# CONNECTIONS.net
KiCad netlist of a schematic drawn in Altium Designer
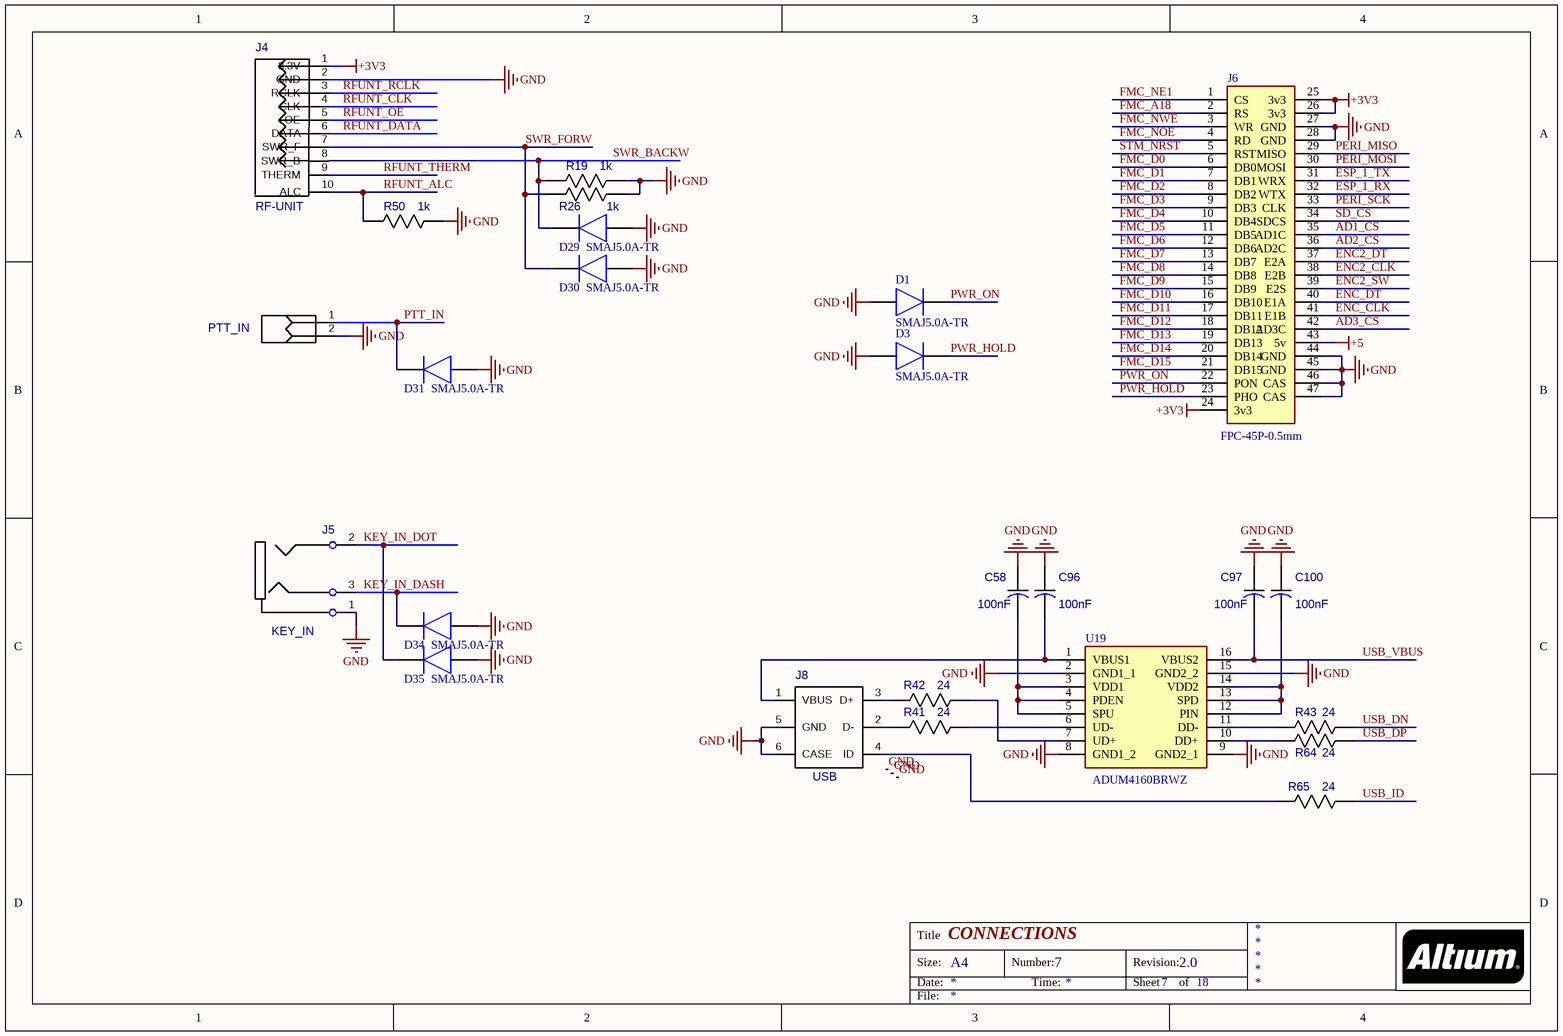
[diagram p0: CONNECTIONS.SchDoc]

(export (version "E")
  (design (tool "Eeschema 10.0.6"))
  (components
    (comp (ref "C58")
      (value "100nF")
      (footprint "CAP_0805")
      (description "CAP_0805")
      (libsource (lib "*") (part "CAP_0805"))
    )
    (comp (ref "C96")
      (value "100nF")
      (footprint "CAP_0805")
      (description "CAP_0805")
      (libsource (lib "*") (part "CAP_0805"))
    )
    (comp (ref "C97")
      (value "100nF")
      (footprint "CAP_0805")
      (description "CAP_0805")
      (libsource (lib "*") (part "CAP_0805"))
    )
    (comp (ref "C100")
      (value "100nF")
      (footprint "CAP_0805")
      (description "CAP_0805")
      (libsource (lib "*") (part "CAP_0805"))
    )
    (comp (ref "D1")
      (value "SMAJ5.0A-TR")
      (footprint "SMBJ36CATR")
      (description "Diode")
      (fields
        (field (name "MANUFACTURER_PART_NUMBER") "SMLVT3V3")
        (field (name "MOUSER PART NUMBER") "511-SMLVT3V3")
      )
      (libsource (lib "*") (part "SMLVT3V3"))
    )
    (comp (ref "D3")
      (value "SMAJ5.0A-TR")
      (footprint "SMBJ36CATR")
      (description "Diode")
      (fields
        (field (name "MANUFACTURER_PART_NUMBER") "SMLVT3V3")
        (field (name "MOUSER PART NUMBER") "511-SMLVT3V3")
      )
      (libsource (lib "*") (part "SMLVT3V3"))
    )
    (comp (ref "D29")
      (value "SMAJ5.0A-TR")
      (footprint "SamacSys:SMBJ36CATR")
      (description "Diode")
      (fields
        (field (name "MANUFACTURER_PART_NUMBER") "SMLVT3V3")
        (field (name "MOUSER PART NUMBER") "511-SMLVT3V3")
      )
      (libsource (lib "*") (part "SMLVT3V3"))
    )
    (comp (ref "D30")
      (value "SMAJ5.0A-TR")
      (footprint "SMBJ36CATR")
      (description "Diode")
      (fields
        (field (name "MANUFACTURER_PART_NUMBER") "SMLVT3V3")
        (field (name "MOUSER PART NUMBER") "511-SMLVT3V3")
      )
      (libsource (lib "*") (part "SMLVT3V3"))
    )
    (comp (ref "D31")
      (value "SMAJ5.0A-TR")
      (footprint "SamacSys:SMBJ36CATR")
      (description "Diode")
      (fields
        (field (name "MANUFACTURER_PART_NUMBER") "SMLVT3V3")
        (field (name "MOUSER PART NUMBER") "511-SMLVT3V3")
      )
      (libsource (lib "*") (part "SMLVT3V3"))
    )
    (comp (ref "D34")
      (value "SMAJ5.0A-TR")
      (footprint "SamacSys:SMBJ36CATR")
      (description "Diode")
      (fields
        (field (name "MANUFACTURER_PART_NUMBER") "SMLVT3V3")
        (field (name "MOUSER PART NUMBER") "511-SMLVT3V3")
      )
      (libsource (lib "*") (part "SMLVT3V3"))
    )
    (comp (ref "D35")
      (value "SMAJ5.0A-TR")
      (footprint "SamacSys:SMBJ36CATR")
      (description "Diode")
      (fields
        (field (name "MANUFACTURER_PART_NUMBER") "SMLVT3V3")
        (field (name "MOUSER PART NUMBER") "511-SMLVT3V3")
      )
      (libsource (lib "*") (part "SMLVT3V3"))
    )
    (comp (ref "J4")
      (value "RF-UNIT")
      (footprint "90131-0126")
      (description "2*5 Pin")
      (libsource (lib "MOTHERBOARD") (part "90131-0126"))
    )
    (comp (ref "J5")
      (value "KEY_IN")
      (footprint "SJ1-3525NG")
      (description "SJ1-3525NG")
      (libsource (lib "*") (part "SJ1-3523N"))
    )
    (comp (ref "J6")
      (value "FPC-45P-0.5mm")
      (footprint "MOTHERBOARD:FH12S45S05SH60")
      (description "Connector")
      (fields
        (field (name "MANUFACTURER_PART_NUMBER") "FH12S-45S-0.5SH(55)")
        (field (name "MOUSER PART NUMBER") "798-FH12S-45S-05SH55")
      )
      (libsource (lib "*") (part "FH12S-45S-0.5SH_55_"))
    )
    (comp (ref "J8")
      (value "USB")
      (footprint "2-1734035-3")
      (description "2-1734035-3")
      (libsource (lib "*") (part "2-1734035-3"))
    )
    (comp (ref "PTT_IN")
      (value "PTT_IN")
      (footprint "51022-0200")
      (description "51022-0200")
      (libsource (lib "*") (part "51022-0200"))
    )
    (comp (ref "R19")
      (value "1k")
      (footprint "RES_0805")
      (description "RES_0805")
      (libsource (lib "*") (part "RES_0805"))
    )
    (comp (ref "R26")
      (value "1k")
      (footprint "RES_0805")
      (description "RES_0805")
      (libsource (lib "*") (part "RES_0805"))
    )
    (comp (ref "R41")
      (value "24")
      (footprint "RES_0805")
      (description "RES_0805")
      (libsource (lib "*") (part "RES_0805"))
    )
    (comp (ref "R42")
      (value "24")
      (footprint "RES_0805")
      (description "RES_0805")
      (libsource (lib "*") (part "RES_0805"))
    )
    (comp (ref "R43")
      (value "24")
      (footprint "RES_0805")
      (description "RES_0805")
      (libsource (lib "*") (part "RES_0805"))
    )
    (comp (ref "R50")
      (value "1k")
      (footprint "RES_0805")
      (description "RES_0805")
      (libsource (lib "*") (part "RES_0805"))
    )
    (comp (ref "R64")
      (value "24")
      (footprint "RES_0805")
      (description "RES_0805")
      (libsource (lib "*") (part "RES_0805"))
    )
    (comp (ref "R65")
      (value "24")
      (footprint "RES_0805")
      (description "RES_0805")
      (libsource (lib "*") (part "RES_0805"))
    )
    (comp (ref "U19")
      (value "ADUM4160BRWZ")
      (footprint "SOIC127P1032X265-16N")
      (description "Integrated Circuit")
      (fields (field (name "MOUSER PART NUMBER") "584-ADUM4160BRWZ"))
      (libsource (lib "*") (part "ADUM4160BRWZ"))
    )
  )
  (nets
    (net (code "1") (name "+3V3") (class "Default")
      (node (ref "J4") (pin "1") (pinfunction "3.3V_1") (pintype "passive"))
      (node (ref "J6") (pin "24") (pinfunction "3v3_24") (pintype "passive"))
      (node (ref "J6") (pin "25") (pinfunction "3v3_25") (pintype "passive"))
      (node (ref "J6") (pin "26") (pinfunction "3v3_26") (pintype "passive"))
    )
    (net (code "2") (name "+5") (class "Default")
      (node (ref "J6") (pin "43") (pinfunction "5v_43") (pintype "passive"))
    )
    (net (code "3") (name "/AD1_CS") (class "Default")
      (node (ref "J6") (pin "35") (pinfunction "AD1C_35") (pintype "passive"))
    )
    (net (code "4") (name "/AD2_CS") (class "Default")
      (node (ref "J6") (pin "36") (pinfunction "AD2C_36") (pintype "passive"))
    )
    (net (code "5") (name "/AD3_CS") (class "Default")
      (node (ref "J6") (pin "42") (pinfunction "AD3C_42") (pintype "passive"))
    )
    (net (code "6") (name "/ENC2_CLK") (class "Default")
      (node (ref "J6") (pin "38") (pinfunction "E2B_38") (pintype "passive"))
    )
    (net (code "7") (name "/ENC2_DT") (class "Default")
      (node (ref "J6") (pin "37") (pinfunction "E2A_37") (pintype "passive"))
    )
    (net (code "8") (name "/ENC2_SW") (class "Default")
      (node (ref "J6") (pin "39") (pinfunction "E2S_39") (pintype "passive"))
    )
    (net (code "9") (name "/ENC_CLK") (class "Default")
      (node (ref "J6") (pin "41") (pinfunction "E1B_41") (pintype "passive"))
    )
    (net (code "10") (name "/ENC_DT") (class "Default")
      (node (ref "J6") (pin "40") (pinfunction "E1A_40") (pintype "passive"))
    )
    (net (code "11") (name "/ESP_1_RX") (class "Default")
      (node (ref "J6") (pin "32") (pinfunction "WTX_32") (pintype "passive"))
    )
    (net (code "12") (name "/ESP_1_TX") (class "Default")
      (node (ref "J6") (pin "31") (pinfunction "WRX_31") (pintype "passive"))
    )
    (net (code "13") (name "/FMC_A18") (class "Default")
      (node (ref "J6") (pin "2") (pinfunction "RS_2") (pintype "passive"))
    )
    (net (code "14") (name "/FMC_D0") (class "Default")
      (node (ref "J6") (pin "6") (pinfunction "DB0_6") (pintype "passive"))
    )
    (net (code "15") (name "/FMC_D1") (class "Default")
      (node (ref "J6") (pin "7") (pinfunction "DB1_7") (pintype "passive"))
    )
    (net (code "16") (name "/FMC_D2") (class "Default")
      (node (ref "J6") (pin "8") (pinfunction "DB2_8") (pintype "passive"))
    )
    (net (code "17") (name "/FMC_D3") (class "Default")
      (node (ref "J6") (pin "9") (pinfunction "DB3_9") (pintype "passive"))
    )
    (net (code "18") (name "/FMC_D4") (class "Default")
      (node (ref "J6") (pin "10") (pinfunction "DB4_10") (pintype "passive"))
    )
    (net (code "19") (name "/FMC_D5") (class "Default")
      (node (ref "J6") (pin "11") (pinfunction "DB5_11") (pintype "passive"))
    )
    (net (code "20") (name "/FMC_D6") (class "Default")
      (node (ref "J6") (pin "12") (pinfunction "DB6_12") (pintype "passive"))
    )
    (net (code "21") (name "/FMC_D7") (class "Default")
      (node (ref "J6") (pin "13") (pinfunction "DB7_13") (pintype "passive"))
    )
    (net (code "22") (name "/FMC_D8") (class "Default")
      (node (ref "J6") (pin "14") (pinfunction "DB8_14") (pintype "passive"))
    )
    (net (code "23") (name "/FMC_D9") (class "Default")
      (node (ref "J6") (pin "15") (pinfunction "DB9_15") (pintype "passive"))
    )
    (net (code "24") (name "/FMC_D10") (class "Default")
      (node (ref "J6") (pin "16") (pinfunction "DB10_16") (pintype "passive"))
    )
    (net (code "25") (name "/FMC_D11") (class "Default")
      (node (ref "J6") (pin "17") (pinfunction "DB11_17") (pintype "passive"))
    )
    (net (code "26") (name "/FMC_D12") (class "Default")
      (node (ref "J6") (pin "18") (pinfunction "DB12_18") (pintype "passive"))
    )
    (net (code "27") (name "/FMC_D13") (class "Default")
      (node (ref "J6") (pin "19") (pinfunction "DB13_19") (pintype "passive"))
    )
    (net (code "28") (name "/FMC_D14") (class "Default")
      (node (ref "J6") (pin "20") (pinfunction "DB14_20") (pintype "passive"))
    )
    (net (code "29") (name "/FMC_D15") (class "Default")
      (node (ref "J6") (pin "21") (pinfunction "DB15_21") (pintype "passive"))
    )
    (net (code "30") (name "/FMC_NE1") (class "Default")
      (node (ref "J6") (pin "1") (pinfunction "CS_1") (pintype "passive"))
    )
    (net (code "31") (name "/FMC_NOE") (class "Default")
      (node (ref "J6") (pin "4") (pinfunction "RD_4") (pintype "passive"))
    )
    (net (code "32") (name "/FMC_NWE") (class "Default")
      (node (ref "J6") (pin "3") (pinfunction "WR_3") (pintype "passive"))
    )
    (net (code "33") (name "/KEY_IN_DASH") (class "Default")
      (node (ref "D34") (pin "1") (pinfunction "K_1") (pintype "passive"))
      (node (ref "J5") (pin "3") (pinfunction "ring_3") (pintype "passive"))
    )
    (net (code "34") (name "/KEY_IN_DOT") (class "Default")
      (node (ref "D35") (pin "1") (pinfunction "K_1") (pintype "passive"))
      (node (ref "J5") (pin "2") (pinfunction "tip_2") (pintype "passive"))
    )
    (net (code "35") (name "/PERI_MISO") (class "Default")
      (node (ref "J6") (pin "29") (pinfunction "MISO_29") (pintype "passive"))
    )
    (net (code "36") (name "/PERI_MOSI") (class "Default")
      (node (ref "J6") (pin "30") (pinfunction "MOSI_30") (pintype "passive"))
    )
    (net (code "37") (name "/PERI_SCK") (class "Default")
      (node (ref "J6") (pin "33") (pinfunction "CLK_33") (pintype "passive"))
    )
    (net (code "38") (name "/PTT_IN") (class "Default")
      (node (ref "D31") (pin "1") (pinfunction "K_1") (pintype "passive"))
      (node (ref "PTT_IN") (pin "1") (pinfunction "1_1") (pintype "passive"))
    )
    (net (code "39") (name "/PWR_HOLD") (class "Default")
      (node (ref "D3") (pin "1") (pinfunction "K_1") (pintype "passive"))
      (node (ref "J6") (pin "23") (pinfunction "PHO_23") (pintype "passive"))
    )
    (net (code "40") (name "/PWR_ON") (class "Default")
      (node (ref "D1") (pin "1") (pinfunction "K_1") (pintype "passive"))
      (node (ref "J6") (pin "22") (pinfunction "PON_22") (pintype "passive"))
    )
    (net (code "41") (name "/RFUNT_ALC") (class "Default")
      (node (ref "J4") (pin "10") (pinfunction "ALC_10") (pintype "passive"))
      (node (ref "R50") (pin "1") (pinfunction "1_1") (pintype "passive"))
    )
    (net (code "42") (name "/RFUNT_CLK") (class "Default")
      (node (ref "J4") (pin "4") (pinfunction "CLK_4") (pintype "passive"))
    )
    (net (code "43") (name "/RFUNT_DATA") (class "Default")
      (node (ref "J4") (pin "6") (pinfunction "DATA_6") (pintype "passive"))
    )
    (net (code "44") (name "/RFUNT_OE") (class "Default")
      (node (ref "J4") (pin "5") (pinfunction "OE_5") (pintype "passive"))
    )
    (net (code "45") (name "/RFUNT_RCLK") (class "Default")
      (node (ref "J4") (pin "3") (pinfunction "RCLK_3") (pintype "passive"))
    )
    (net (code "46") (name "/RFUNT_THERM") (class "Default")
      (node (ref "J4") (pin "9") (pinfunction "THERM_9") (pintype "passive"))
    )
    (net (code "47") (name "/SD_CS") (class "Default")
      (node (ref "J6") (pin "34") (pinfunction "SDCS_34") (pintype "passive"))
    )
    (net (code "48") (name "/STM_NRST") (class "Default")
      (node (ref "J6") (pin "5") (pinfunction "RST_5") (pintype "passive"))
    )
    (net (code "49") (name "/SWR_BACKW") (class "Default")
      (node (ref "D29") (pin "1") (pinfunction "K_1") (pintype "passive"))
      (node (ref "J4") (pin "8") (pinfunction "SWR_B_8") (pintype "passive"))
      (node (ref "R19") (pin "1") (pinfunction "1_1") (pintype "passive"))
    )
    (net (code "50") (name "/SWR_FORW") (class "Default")
      (node (ref "D30") (pin "1") (pinfunction "K_1") (pintype "passive"))
      (node (ref "J4") (pin "7") (pinfunction "SWR_F_7") (pintype "passive"))
      (node (ref "R26") (pin "1") (pinfunction "1_1") (pintype "passive"))
    )
    (net (code "51") (name "/USB_DN") (class "Default")
      (node (ref "R43") (pin "2") (pinfunction "2_2") (pintype "passive"))
    )
    (net (code "52") (name "/USB_DP") (class "Default")
      (node (ref "R64") (pin "2") (pinfunction "2_2") (pintype "passive"))
    )
    (net (code "53") (name "/USB_ID") (class "Default")
      (node (ref "R65") (pin "2") (pinfunction "2_2") (pintype "passive"))
    )
    (net (code "54") (name "/USB_VBUS") (class "Default")
      (node (ref "C97") (pin "2") (pinfunction "2_2") (pintype "passive"))
      (node (ref "U19") (pin "16") (pinfunction "VBUS2_16") (pintype "passive"))
    )
    (net (code "55") (name "GND") (class "Default")
      (node (ref "C100") (pin "1") (pinfunction "1_1") (pintype "passive"))
      (node (ref "C58") (pin "1") (pinfunction "1_1") (pintype "passive"))
      (node (ref "C96") (pin "1") (pinfunction "1_1") (pintype "passive"))
      (node (ref "C97") (pin "1") (pinfunction "1_1") (pintype "passive"))
      (node (ref "D1") (pin "2") (pinfunction "A_2") (pintype "passive"))
      (node (ref "D29") (pin "2") (pinfunction "A_2") (pintype "passive"))
      (node (ref "D3") (pin "2") (pinfunction "A_2") (pintype "passive"))
      (node (ref "D30") (pin "2") (pinfunction "A_2") (pintype "passive"))
      (node (ref "D31") (pin "2") (pinfunction "A_2") (pintype "passive"))
      (node (ref "D34") (pin "2") (pinfunction "A_2") (pintype "passive"))
      (node (ref "D35") (pin "2") (pinfunction "A_2") (pintype "passive"))
      (node (ref "J4") (pin "2") (pinfunction "GND_2") (pintype "passive"))
      (node (ref "J5") (pin "1") (pinfunction "sleeve_1") (pintype "passive"))
      (node (ref "J6") (pin "27") (pinfunction "GND_27") (pintype "passive"))
      (node (ref "J6") (pin "28") (pinfunction "GND_28") (pintype "passive"))
      (node (ref "J6") (pin "44") (pinfunction "GND_44") (pintype "passive"))
      (node (ref "J6") (pin "45") (pinfunction "GND_45") (pintype "passive"))
      (node (ref "J6") (pin "46") (pinfunction "CAS_46") (pintype "passive"))
      (node (ref "J6") (pin "47") (pinfunction "CAS_47") (pintype "passive"))
      (node (ref "J8") (pin "5") (pinfunction "GND_5") (pintype "passive"))
      (node (ref "J8") (pin "6") (pinfunction "CASE_6") (pintype "passive"))
      (node (ref "J8") (pin "7") (pinfunction "0_7") (pintype "passive"))
      (node (ref "J8") (pin "8") (pinfunction "0_8") (pintype "passive"))
      (node (ref "J8") (pin "9") (pinfunction "0_9") (pintype "passive"))
      (node (ref "PTT_IN") (pin "2") (pinfunction "2_2") (pintype "passive"))
      (node (ref "R19") (pin "2") (pinfunction "2_2") (pintype "passive"))
      (node (ref "R26") (pin "2") (pinfunction "2_2") (pintype "passive"))
      (node (ref "R50") (pin "2") (pinfunction "2_2") (pintype "passive"))
      (node (ref "U19") (pin "15") (pinfunction "GND2_2_15") (pintype "passive"))
      (node (ref "U19") (pin "2") (pinfunction "GND1_1_2") (pintype "passive"))
      (node (ref "U19") (pin "8") (pinfunction "GND1_2_8") (pintype "passive"))
      (node (ref "U19") (pin "9") (pinfunction "GND2_1_9") (pintype "passive"))
    )
    (net (code "56") (name "Net-(J8-D+)") (class "Default")
      (node (ref "J8") (pin "3") (pinfunction "D+_3") (pintype "passive"))
      (node (ref "R42") (pin "1") (pinfunction "1_1") (pintype "passive"))
    )
    (net (code "57") (name "Net-(J8-D-)") (class "Default")
      (node (ref "J8") (pin "2") (pinfunction "D-_2") (pintype "passive"))
      (node (ref "R41") (pin "1") (pinfunction "1_1") (pintype "passive"))
    )
    (net (code "58") (name "Net-(J8-ID)") (class "Default")
      (node (ref "J8") (pin "4") (pinfunction "ID_4") (pintype "passive"))
      (node (ref "R65") (pin "1") (pinfunction "1_1") (pintype "passive"))
    )
    (net (code "59") (name "Net-(J8-VBUS)") (class "Default")
      (node (ref "C96") (pin "2") (pinfunction "2_2") (pintype "passive"))
      (node (ref "J8") (pin "1") (pinfunction "VBUS_1") (pintype "passive"))
      (node (ref "U19") (pin "1") (pinfunction "VBUS1_1") (pintype "passive"))
    )
    (net (code "60") (name "Net-(U19-DD+)") (class "Default")
      (node (ref "R64") (pin "1") (pinfunction "1_1") (pintype "passive"))
      (node (ref "U19") (pin "10") (pinfunction "DD+_10") (pintype "passive"))
    )
    (net (code "61") (name "Net-(U19-DD-)") (class "Default")
      (node (ref "R43") (pin "1") (pinfunction "1_1") (pintype "passive"))
      (node (ref "U19") (pin "11") (pinfunction "DD-_11") (pintype "passive"))
    )
    (net (code "62") (name "Net-(U19-PDEN)") (class "Default")
      (node (ref "C58") (pin "2") (pinfunction "2_2") (pintype "passive"))
      (node (ref "U19") (pin "3") (pinfunction "VDD1_3") (pintype "passive"))
      (node (ref "U19") (pin "4") (pinfunction "PDEN_4") (pintype "passive"))
      (node (ref "U19") (pin "5") (pinfunction "SPU_5") (pintype "passive"))
    )
    (net (code "63") (name "Net-(U19-PIN)") (class "Default")
      (node (ref "C100") (pin "2") (pinfunction "2_2") (pintype "passive"))
      (node (ref "U19") (pin "12") (pinfunction "PIN_12") (pintype "passive"))
      (node (ref "U19") (pin "13") (pinfunction "SPD_13") (pintype "passive"))
      (node (ref "U19") (pin "14") (pinfunction "VDD2_14") (pintype "passive"))
    )
    (net (code "64") (name "Net-(U19-UD+)") (class "Default")
      (node (ref "R42") (pin "2") (pinfunction "2_2") (pintype "passive"))
      (node (ref "U19") (pin "7") (pinfunction "UD+_7") (pintype "passive"))
    )
    (net (code "65") (name "Net-(U19-UD-)") (class "Default")
      (node (ref "R41") (pin "2") (pinfunction "2_2") (pintype "passive"))
      (node (ref "U19") (pin "6") (pinfunction "UD-_6") (pintype "passive"))
    )
  )
)
